# clock_led.net
KiCad netlist of a schematic drawn in Altium Designer
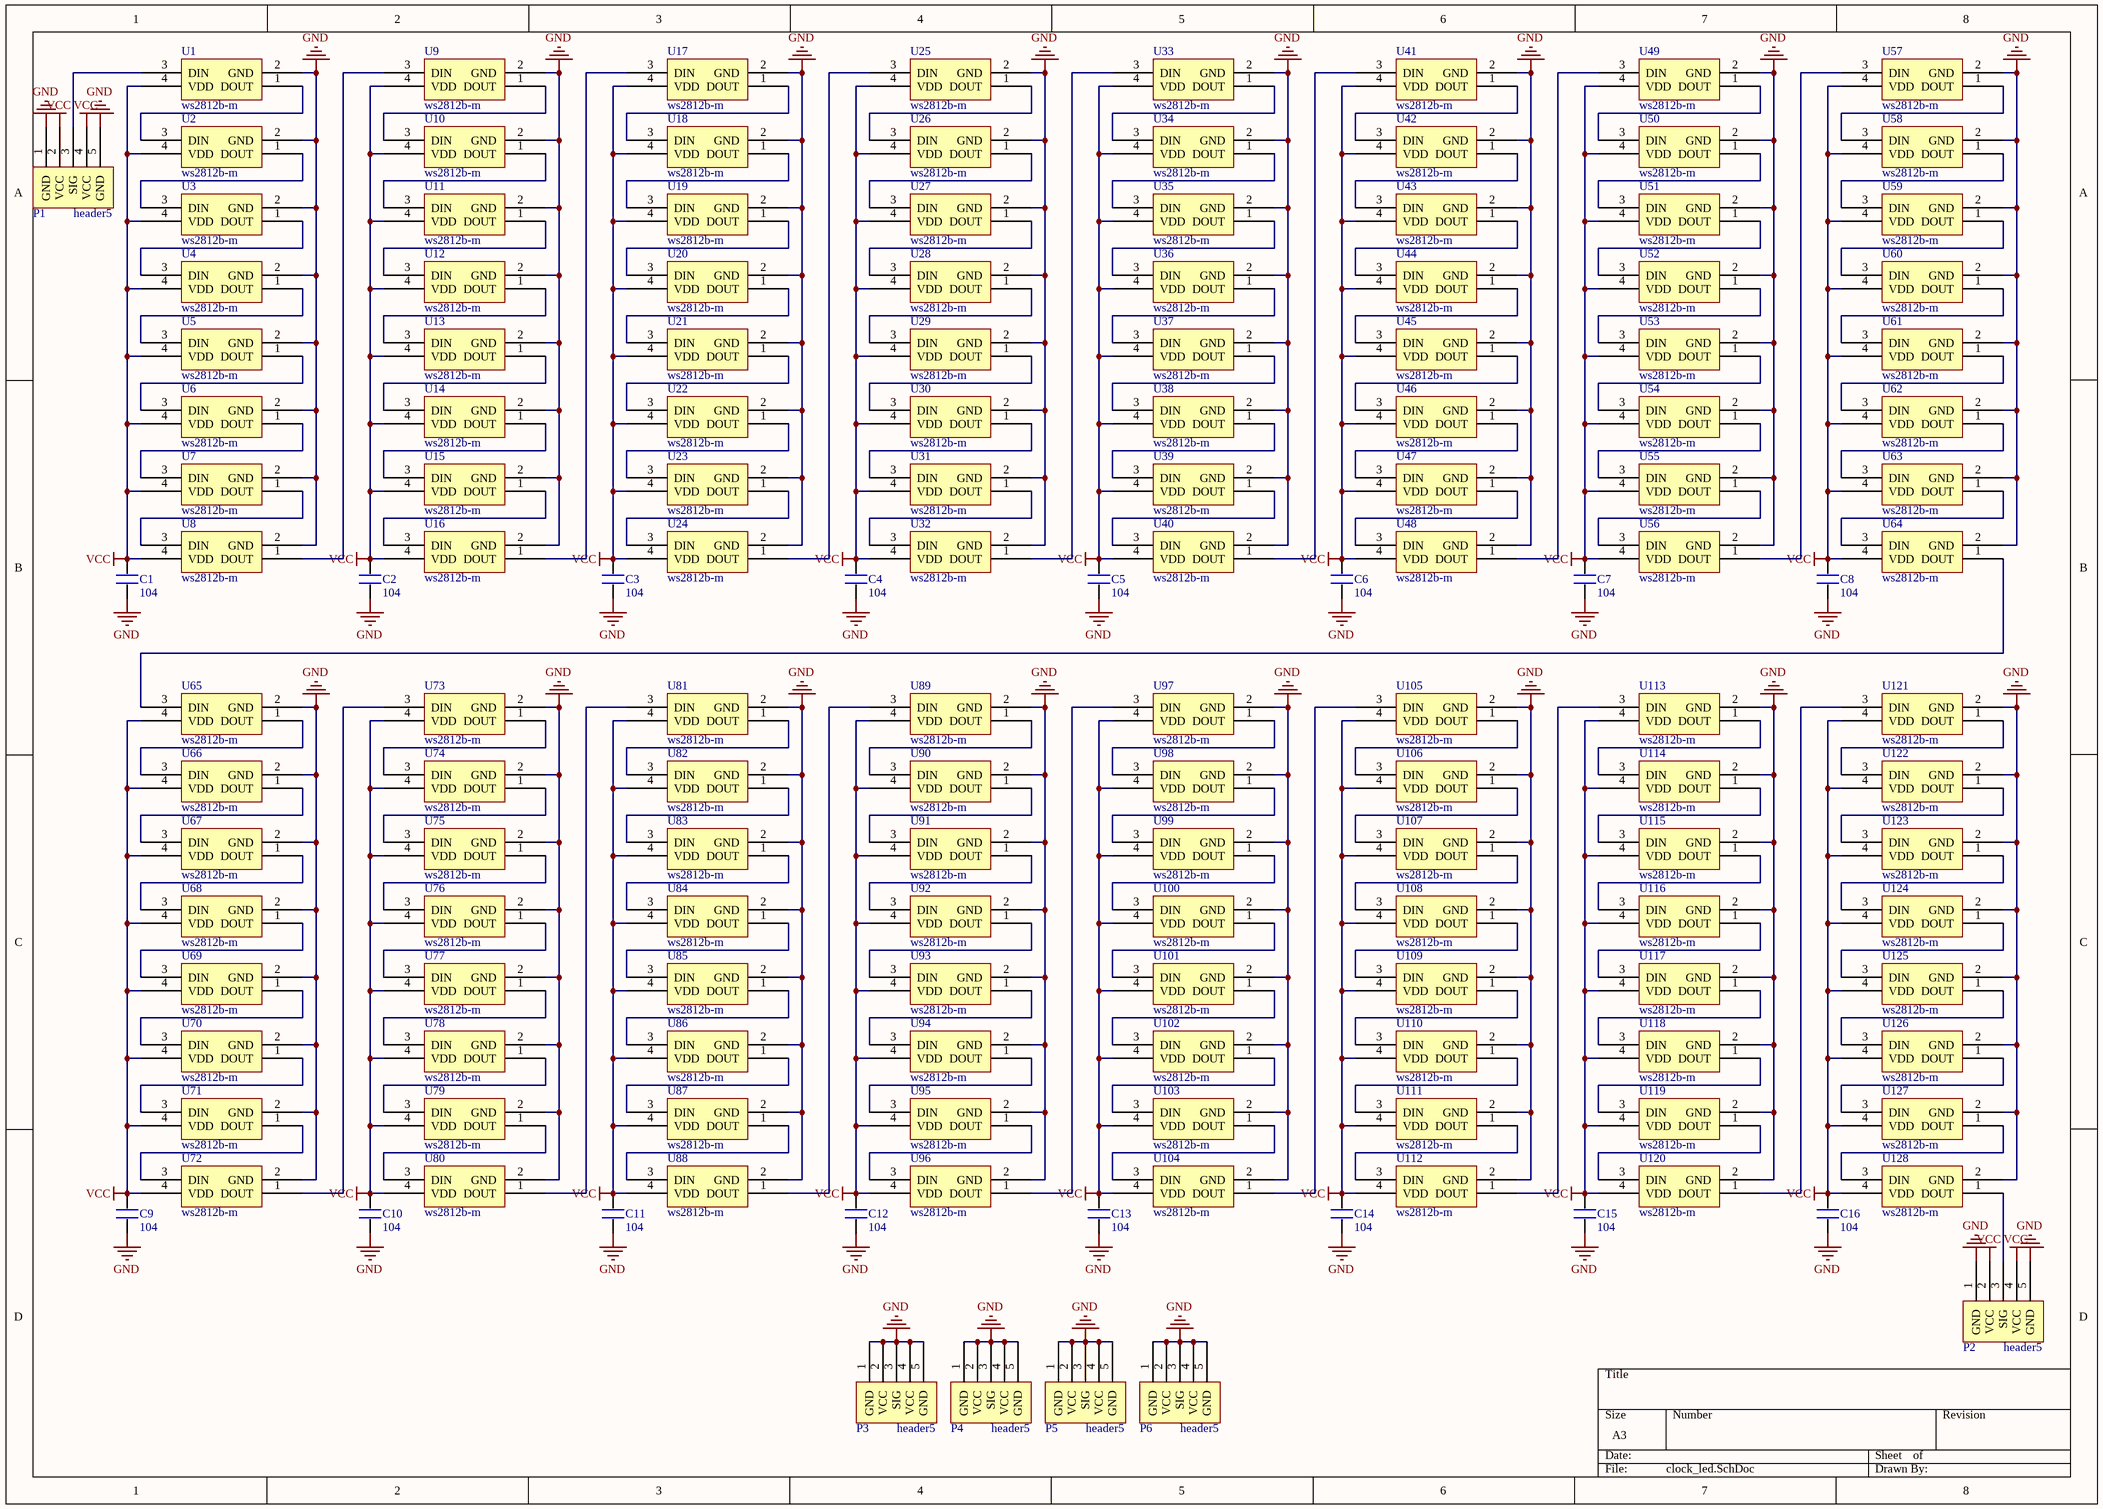
[diagram p0: clock_led.SchDoc]

(export (version "E")
  (design (tool "Eeschema 10.0.6"))
  (components
    (comp (ref "C1") (value "104") (footprint "0603P") (libsource (lib "WarShip V3 STM32103封装库") (part "C")))
    (comp (ref "C2") (value "104") (footprint "0603P") (libsource (lib "WarShip V3 STM32103封装库") (part "C")))
    (comp (ref "C3") (value "104") (footprint "0603P") (libsource (lib "WarShip V3 STM32103封装库") (part "C")))
    (comp (ref "C4") (value "104") (footprint "0603P") (libsource (lib "WarShip V3 STM32103封装库") (part "C")))
    (comp (ref "C5") (value "104") (footprint "0603P") (libsource (lib "WarShip V3 STM32103封装库") (part "C")))
    (comp (ref "C6") (value "104") (footprint "0603P") (libsource (lib "WarShip V3 STM32103封装库") (part "C")))
    (comp (ref "C7") (value "104") (footprint "0603P") (libsource (lib "WarShip V3 STM32103封装库") (part "C")))
    (comp (ref "C8") (value "104") (footprint "0603P") (libsource (lib "WarShip V3 STM32103封装库") (part "C")))
    (comp (ref "C9") (value "104") (footprint "0603P") (libsource (lib "WarShip V3 STM32103封装库") (part "C")))
    (comp (ref "C10") (value "104") (footprint "0603P") (libsource (lib "WarShip V3 STM32103封装库") (part "C")))
    (comp (ref "C11") (value "104") (footprint "0603P") (libsource (lib "WarShip V3 STM32103封装库") (part "C")))
    (comp (ref "C12") (value "104") (footprint "0603P") (libsource (lib "WarShip V3 STM32103封装库") (part "C")))
    (comp (ref "C13") (value "104") (footprint "0603P") (libsource (lib "WarShip V3 STM32103封装库") (part "C")))
    (comp (ref "C14") (value "104") (footprint "0603P") (libsource (lib "WarShip V3 STM32103封装库") (part "C")))
    (comp (ref "C15") (value "104") (footprint "0603P") (libsource (lib "WarShip V3 STM32103封装库") (part "C")))
    (comp (ref "C16") (value "104") (footprint "0603P") (libsource (lib "WarShip V3 STM32103封装库") (part "C")))
    (comp (ref "P1") (value "header5") (footprint "header5") (libsource (lib "clock") (part "header5")))
    (comp (ref "P2") (value "header5") (footprint "header5") (libsource (lib "clock") (part "header5")))
    (comp (ref "P3") (value "header5") (footprint "header5") (libsource (lib "clock") (part "header5")))
    (comp (ref "P4") (value "header5") (footprint "header5") (libsource (lib "clock") (part "header5")))
    (comp (ref "P5") (value "header5") (footprint "header5") (libsource (lib "clock") (part "header5")))
    (comp (ref "P6") (value "header5") (footprint "header5") (libsource (lib "clock") (part "header5")))
    (comp (ref "U1")
      (value "ws2812b-m")
      (footprint "WS2812B-MINI")
      (libsource (lib "clock") (part "WS2812B-MINI"))
    )
    (comp (ref "U2")
      (value "ws2812b-m")
      (footprint "WS2812B-MINI")
      (libsource (lib "clock") (part "WS2812B-MINI"))
    )
    (comp (ref "U3")
      (value "ws2812b-m")
      (footprint "WS2812B-MINI")
      (libsource (lib "clock") (part "WS2812B-MINI"))
    )
    (comp (ref "U4")
      (value "ws2812b-m")
      (footprint "WS2812B-MINI")
      (libsource (lib "clock") (part "WS2812B-MINI"))
    )
    (comp (ref "U5")
      (value "ws2812b-m")
      (footprint "WS2812B-MINI")
      (libsource (lib "clock") (part "WS2812B-MINI"))
    )
    (comp (ref "U6")
      (value "ws2812b-m")
      (footprint "WS2812B-MINI")
      (libsource (lib "clock") (part "WS2812B-MINI"))
    )
    (comp (ref "U7")
      (value "ws2812b-m")
      (footprint "WS2812B-MINI")
      (libsource (lib "clock") (part "WS2812B-MINI"))
    )
    (comp (ref "U8")
      (value "ws2812b-m")
      (footprint "WS2812B-MINI")
      (libsource (lib "clock") (part "WS2812B-MINI"))
    )
    (comp (ref "U9")
      (value "ws2812b-m")
      (footprint "WS2812B-MINI")
      (libsource (lib "clock") (part "WS2812B-MINI"))
    )
    (comp (ref "U10")
      (value "ws2812b-m")
      (footprint "WS2812B-MINI")
      (libsource (lib "clock") (part "WS2812B-MINI"))
    )
    (comp (ref "U11")
      (value "ws2812b-m")
      (footprint "WS2812B-MINI")
      (libsource (lib "clock") (part "WS2812B-MINI"))
    )
    (comp (ref "U12")
      (value "ws2812b-m")
      (footprint "WS2812B-MINI")
      (libsource (lib "clock") (part "WS2812B-MINI"))
    )
    (comp (ref "U13")
      (value "ws2812b-m")
      (footprint "WS2812B-MINI")
      (libsource (lib "clock") (part "WS2812B-MINI"))
    )
    (comp (ref "U14")
      (value "ws2812b-m")
      (footprint "WS2812B-MINI")
      (libsource (lib "clock") (part "WS2812B-MINI"))
    )
    (comp (ref "U15")
      (value "ws2812b-m")
      (footprint "WS2812B-MINI")
      (libsource (lib "clock") (part "WS2812B-MINI"))
    )
    (comp (ref "U16")
      (value "ws2812b-m")
      (footprint "WS2812B-MINI")
      (libsource (lib "clock") (part "WS2812B-MINI"))
    )
    (comp (ref "U17")
      (value "ws2812b-m")
      (footprint "WS2812B-MINI")
      (libsource (lib "clock") (part "WS2812B-MINI"))
    )
    (comp (ref "U18")
      (value "ws2812b-m")
      (footprint "WS2812B-MINI")
      (libsource (lib "clock") (part "WS2812B-MINI"))
    )
    (comp (ref "U19")
      (value "ws2812b-m")
      (footprint "WS2812B-MINI")
      (libsource (lib "clock") (part "WS2812B-MINI"))
    )
    (comp (ref "U20")
      (value "ws2812b-m")
      (footprint "WS2812B-MINI")
      (libsource (lib "clock") (part "WS2812B-MINI"))
    )
    (comp (ref "U21")
      (value "ws2812b-m")
      (footprint "WS2812B-MINI")
      (libsource (lib "clock") (part "WS2812B-MINI"))
    )
    (comp (ref "U22")
      (value "ws2812b-m")
      (footprint "WS2812B-MINI")
      (libsource (lib "clock") (part "WS2812B-MINI"))
    )
    (comp (ref "U23")
      (value "ws2812b-m")
      (footprint "WS2812B-MINI")
      (libsource (lib "clock") (part "WS2812B-MINI"))
    )
    (comp (ref "U24")
      (value "ws2812b-m")
      (footprint "WS2812B-MINI")
      (libsource (lib "clock") (part "WS2812B-MINI"))
    )
    (comp (ref "U25")
      (value "ws2812b-m")
      (footprint "WS2812B-MINI")
      (libsource (lib "clock") (part "WS2812B-MINI"))
    )
    (comp (ref "U26")
      (value "ws2812b-m")
      (footprint "WS2812B-MINI")
      (libsource (lib "clock") (part "WS2812B-MINI"))
    )
    (comp (ref "U27")
      (value "ws2812b-m")
      (footprint "WS2812B-MINI")
      (libsource (lib "clock") (part "WS2812B-MINI"))
    )
    (comp (ref "U28")
      (value "ws2812b-m")
      (footprint "WS2812B-MINI")
      (libsource (lib "clock") (part "WS2812B-MINI"))
    )
    (comp (ref "U29")
      (value "ws2812b-m")
      (footprint "WS2812B-MINI")
      (libsource (lib "clock") (part "WS2812B-MINI"))
    )
    (comp (ref "U30")
      (value "ws2812b-m")
      (footprint "WS2812B-MINI")
      (libsource (lib "clock") (part "WS2812B-MINI"))
    )
    (comp (ref "U31")
      (value "ws2812b-m")
      (footprint "WS2812B-MINI")
      (libsource (lib "clock") (part "WS2812B-MINI"))
    )
    (comp (ref "U32")
      (value "ws2812b-m")
      (footprint "WS2812B-MINI")
      (libsource (lib "clock") (part "WS2812B-MINI"))
    )
    (comp (ref "U33")
      (value "ws2812b-m")
      (footprint "WS2812B-MINI")
      (libsource (lib "clock") (part "WS2812B-MINI"))
    )
    (comp (ref "U34")
      (value "ws2812b-m")
      (footprint "WS2812B-MINI")
      (libsource (lib "clock") (part "WS2812B-MINI"))
    )
    (comp (ref "U35")
      (value "ws2812b-m")
      (footprint "WS2812B-MINI")
      (libsource (lib "clock") (part "WS2812B-MINI"))
    )
    (comp (ref "U36")
      (value "ws2812b-m")
      (footprint "WS2812B-MINI")
      (libsource (lib "clock") (part "WS2812B-MINI"))
    )
    (comp (ref "U37")
      (value "ws2812b-m")
      (footprint "WS2812B-MINI")
      (libsource (lib "clock") (part "WS2812B-MINI"))
    )
    (comp (ref "U38")
      (value "ws2812b-m")
      (footprint "WS2812B-MINI")
      (libsource (lib "clock") (part "WS2812B-MINI"))
    )
    (comp (ref "U39")
      (value "ws2812b-m")
      (footprint "WS2812B-MINI")
      (libsource (lib "clock") (part "WS2812B-MINI"))
    )
    (comp (ref "U40")
      (value "ws2812b-m")
      (footprint "WS2812B-MINI")
      (libsource (lib "clock") (part "WS2812B-MINI"))
    )
    (comp (ref "U41")
      (value "ws2812b-m")
      (footprint "WS2812B-MINI")
      (libsource (lib "clock") (part "WS2812B-MINI"))
    )
    (comp (ref "U42")
      (value "ws2812b-m")
      (footprint "WS2812B-MINI")
      (libsource (lib "clock") (part "WS2812B-MINI"))
    )
    (comp (ref "U43")
      (value "ws2812b-m")
      (footprint "WS2812B-MINI")
      (libsource (lib "clock") (part "WS2812B-MINI"))
    )
    (comp (ref "U44")
      (value "ws2812b-m")
      (footprint "WS2812B-MINI")
      (libsource (lib "clock") (part "WS2812B-MINI"))
    )
    (comp (ref "U45")
      (value "ws2812b-m")
      (footprint "WS2812B-MINI")
      (libsource (lib "clock") (part "WS2812B-MINI"))
    )
    (comp (ref "U46")
      (value "ws2812b-m")
      (footprint "WS2812B-MINI")
      (libsource (lib "clock") (part "WS2812B-MINI"))
    )
    (comp (ref "U47")
      (value "ws2812b-m")
      (footprint "WS2812B-MINI")
      (libsource (lib "clock") (part "WS2812B-MINI"))
    )
    (comp (ref "U48")
      (value "ws2812b-m")
      (footprint "WS2812B-MINI")
      (libsource (lib "clock") (part "WS2812B-MINI"))
    )
    (comp (ref "U49")
      (value "ws2812b-m")
      (footprint "WS2812B-MINI")
      (libsource (lib "clock") (part "WS2812B-MINI"))
    )
    (comp (ref "U50")
      (value "ws2812b-m")
      (footprint "WS2812B-MINI")
      (libsource (lib "clock") (part "WS2812B-MINI"))
    )
    (comp (ref "U51")
      (value "ws2812b-m")
      (footprint "WS2812B-MINI")
      (libsource (lib "clock") (part "WS2812B-MINI"))
    )
    (comp (ref "U52")
      (value "ws2812b-m")
      (footprint "WS2812B-MINI")
      (libsource (lib "clock") (part "WS2812B-MINI"))
    )
    (comp (ref "U53")
      (value "ws2812b-m")
      (footprint "WS2812B-MINI")
      (libsource (lib "clock") (part "WS2812B-MINI"))
    )
    (comp (ref "U54")
      (value "ws2812b-m")
      (footprint "WS2812B-MINI")
      (libsource (lib "clock") (part "WS2812B-MINI"))
    )
    (comp (ref "U55")
      (value "ws2812b-m")
      (footprint "WS2812B-MINI")
      (libsource (lib "clock") (part "WS2812B-MINI"))
    )
    (comp (ref "U56")
      (value "ws2812b-m")
      (footprint "WS2812B-MINI")
      (libsource (lib "clock") (part "WS2812B-MINI"))
    )
    (comp (ref "U57")
      (value "ws2812b-m")
      (footprint "WS2812B-MINI")
      (libsource (lib "clock") (part "WS2812B-MINI"))
    )
    (comp (ref "U58")
      (value "ws2812b-m")
      (footprint "WS2812B-MINI")
      (libsource (lib "clock") (part "WS2812B-MINI"))
    )
    (comp (ref "U59")
      (value "ws2812b-m")
      (footprint "WS2812B-MINI")
      (libsource (lib "clock") (part "WS2812B-MINI"))
    )
    (comp (ref "U60")
      (value "ws2812b-m")
      (footprint "WS2812B-MINI")
      (libsource (lib "clock") (part "WS2812B-MINI"))
    )
    (comp (ref "U61")
      (value "ws2812b-m")
      (footprint "WS2812B-MINI")
      (libsource (lib "clock") (part "WS2812B-MINI"))
    )
    (comp (ref "U62")
      (value "ws2812b-m")
      (footprint "WS2812B-MINI")
      (libsource (lib "clock") (part "WS2812B-MINI"))
    )
    (comp (ref "U63")
      (value "ws2812b-m")
      (footprint "WS2812B-MINI")
      (libsource (lib "clock") (part "WS2812B-MINI"))
    )
    (comp (ref "U64")
      (value "ws2812b-m")
      (footprint "WS2812B-MINI")
      (libsource (lib "clock") (part "WS2812B-MINI"))
    )
    (comp (ref "U65")
      (value "ws2812b-m")
      (footprint "WS2812B-MINI")
      (libsource (lib "clock") (part "WS2812B-MINI"))
    )
    (comp (ref "U66")
      (value "ws2812b-m")
      (footprint "WS2812B-MINI")
      (libsource (lib "clock") (part "WS2812B-MINI"))
    )
    (comp (ref "U67")
      (value "ws2812b-m")
      (footprint "WS2812B-MINI")
      (libsource (lib "clock") (part "WS2812B-MINI"))
    )
    (comp (ref "U68")
      (value "ws2812b-m")
      (footprint "WS2812B-MINI")
      (libsource (lib "clock") (part "WS2812B-MINI"))
    )
    (comp (ref "U69")
      (value "ws2812b-m")
      (footprint "WS2812B-MINI")
      (libsource (lib "clock") (part "WS2812B-MINI"))
    )
    (comp (ref "U70")
      (value "ws2812b-m")
      (footprint "WS2812B-MINI")
      (libsource (lib "clock") (part "WS2812B-MINI"))
    )
    (comp (ref "U71")
      (value "ws2812b-m")
      (footprint "WS2812B-MINI")
      (libsource (lib "clock") (part "WS2812B-MINI"))
    )
    (comp (ref "U72")
      (value "ws2812b-m")
      (footprint "WS2812B-MINI")
      (libsource (lib "clock") (part "WS2812B-MINI"))
    )
    (comp (ref "U73")
      (value "ws2812b-m")
      (footprint "WS2812B-MINI")
      (libsource (lib "clock") (part "WS2812B-MINI"))
    )
    (comp (ref "U74")
      (value "ws2812b-m")
      (footprint "WS2812B-MINI")
      (libsource (lib "clock") (part "WS2812B-MINI"))
    )
    (comp (ref "U75")
      (value "ws2812b-m")
      (footprint "WS2812B-MINI")
      (libsource (lib "clock") (part "WS2812B-MINI"))
    )
    (comp (ref "U76")
      (value "ws2812b-m")
      (footprint "WS2812B-MINI")
      (libsource (lib "clock") (part "WS2812B-MINI"))
    )
    (comp (ref "U77")
      (value "ws2812b-m")
      (footprint "WS2812B-MINI")
      (libsource (lib "clock") (part "WS2812B-MINI"))
    )
    (comp (ref "U78")
      (value "ws2812b-m")
      (footprint "WS2812B-MINI")
      (libsource (lib "clock") (part "WS2812B-MINI"))
    )
    (comp (ref "U79")
      (value "ws2812b-m")
      (footprint "WS2812B-MINI")
      (libsource (lib "clock") (part "WS2812B-MINI"))
    )
    (comp (ref "U80")
      (value "ws2812b-m")
      (footprint "WS2812B-MINI")
      (libsource (lib "clock") (part "WS2812B-MINI"))
    )
    (comp (ref "U81")
      (value "ws2812b-m")
      (footprint "WS2812B-MINI")
      (libsource (lib "clock") (part "WS2812B-MINI"))
    )
    (comp (ref "U82")
      (value "ws2812b-m")
      (footprint "WS2812B-MINI")
      (libsource (lib "clock") (part "WS2812B-MINI"))
    )
    (comp (ref "U83")
      (value "ws2812b-m")
      (footprint "WS2812B-MINI")
      (libsource (lib "clock") (part "WS2812B-MINI"))
    )
    (comp (ref "U84")
      (value "ws2812b-m")
      (footprint "WS2812B-MINI")
      (libsource (lib "clock") (part "WS2812B-MINI"))
    )
    (comp (ref "U85")
      (value "ws2812b-m")
      (footprint "WS2812B-MINI")
      (libsource (lib "clock") (part "WS2812B-MINI"))
    )
    (comp (ref "U86")
      (value "ws2812b-m")
      (footprint "WS2812B-MINI")
      (libsource (lib "clock") (part "WS2812B-MINI"))
    )
    (comp (ref "U87")
      (value "ws2812b-m")
      (footprint "WS2812B-MINI")
      (libsource (lib "clock") (part "WS2812B-MINI"))
    )
    (comp (ref "U88")
      (value "ws2812b-m")
      (footprint "WS2812B-MINI")
      (libsource (lib "clock") (part "WS2812B-MINI"))
    )
    (comp (ref "U89")
      (value "ws2812b-m")
      (footprint "WS2812B-MINI")
      (libsource (lib "clock") (part "WS2812B-MINI"))
    )
    (comp (ref "U90")
      (value "ws2812b-m")
      (footprint "WS2812B-MINI")
      (libsource (lib "clock") (part "WS2812B-MINI"))
    )
    (comp (ref "U91")
      (value "ws2812b-m")
      (footprint "WS2812B-MINI")
      (libsource (lib "clock") (part "WS2812B-MINI"))
    )
    (comp (ref "U92")
      (value "ws2812b-m")
      (footprint "WS2812B-MINI")
      (libsource (lib "clock") (part "WS2812B-MINI"))
    )
    (comp (ref "U93")
      (value "ws2812b-m")
      (footprint "WS2812B-MINI")
      (libsource (lib "clock") (part "WS2812B-MINI"))
    )
    (comp (ref "U94")
      (value "ws2812b-m")
      (footprint "WS2812B-MINI")
      (libsource (lib "clock") (part "WS2812B-MINI"))
    )
    (comp (ref "U95")
      (value "ws2812b-m")
      (footprint "WS2812B-MINI")
      (libsource (lib "clock") (part "WS2812B-MINI"))
    )
    (comp (ref "U96")
      (value "ws2812b-m")
      (footprint "WS2812B-MINI")
      (libsource (lib "clock") (part "WS2812B-MINI"))
    )
    (comp (ref "U97")
      (value "ws2812b-m")
      (footprint "WS2812B-MINI")
      (libsource (lib "clock") (part "WS2812B-MINI"))
    )
    (comp (ref "U98")
      (value "ws2812b-m")
      (footprint "WS2812B-MINI")
      (libsource (lib "clock") (part "WS2812B-MINI"))
    )
    (comp (ref "U99")
      (value "ws2812b-m")
      (footprint "WS2812B-MINI")
      (libsource (lib "clock") (part "WS2812B-MINI"))
    )
    (comp (ref "U100")
      (value "ws2812b-m")
      (footprint "WS2812B-MINI")
      (libsource (lib "clock") (part "WS2812B-MINI"))
    )
    (comp (ref "U101")
      (value "ws2812b-m")
      (footprint "WS2812B-MINI")
      (libsource (lib "clock") (part "WS2812B-MINI"))
    )
    (comp (ref "U102")
      (value "ws2812b-m")
      (footprint "WS2812B-MINI")
      (libsource (lib "clock") (part "WS2812B-MINI"))
    )
    (comp (ref "U103")
      (value "ws2812b-m")
      (footprint "WS2812B-MINI")
      (libsource (lib "clock") (part "WS2812B-MINI"))
    )
    (comp (ref "U104")
      (value "ws2812b-m")
      (footprint "WS2812B-MINI")
      (libsource (lib "clock") (part "WS2812B-MINI"))
    )
    (comp (ref "U105")
      (value "ws2812b-m")
      (footprint "WS2812B-MINI")
      (libsource (lib "clock") (part "WS2812B-MINI"))
    )
    (comp (ref "U106")
      (value "ws2812b-m")
      (footprint "WS2812B-MINI")
      (libsource (lib "clock") (part "WS2812B-MINI"))
    )
    (comp (ref "U107")
      (value "ws2812b-m")
      (footprint "WS2812B-MINI")
      (libsource (lib "clock") (part "WS2812B-MINI"))
    )
    (comp (ref "U108")
      (value "ws2812b-m")
      (footprint "WS2812B-MINI")
      (libsource (lib "clock") (part "WS2812B-MINI"))
    )
    (comp (ref "U109")
      (value "ws2812b-m")
      (footprint "WS2812B-MINI")
      (libsource (lib "clock") (part "WS2812B-MINI"))
    )
    (comp (ref "U110")
      (value "ws2812b-m")
      (footprint "WS2812B-MINI")
      (libsource (lib "clock") (part "WS2812B-MINI"))
    )
    (comp (ref "U111")
      (value "ws2812b-m")
      (footprint "WS2812B-MINI")
      (libsource (lib "clock") (part "WS2812B-MINI"))
    )
    (comp (ref "U112")
      (value "ws2812b-m")
      (footprint "WS2812B-MINI")
      (libsource (lib "clock") (part "WS2812B-MINI"))
    )
    (comp (ref "U113")
      (value "ws2812b-m")
      (footprint "WS2812B-MINI")
      (libsource (lib "clock") (part "WS2812B-MINI"))
    )
    (comp (ref "U114")
      (value "ws2812b-m")
      (footprint "WS2812B-MINI")
      (libsource (lib "clock") (part "WS2812B-MINI"))
    )
    (comp (ref "U115")
      (value "ws2812b-m")
      (footprint "WS2812B-MINI")
      (libsource (lib "clock") (part "WS2812B-MINI"))
    )
    (comp (ref "U116")
      (value "ws2812b-m")
      (footprint "WS2812B-MINI")
      (libsource (lib "clock") (part "WS2812B-MINI"))
    )
    (comp (ref "U117")
      (value "ws2812b-m")
      (footprint "WS2812B-MINI")
      (libsource (lib "clock") (part "WS2812B-MINI"))
    )
    (comp (ref "U118")
      (value "ws2812b-m")
      (footprint "WS2812B-MINI")
      (libsource (lib "clock") (part "WS2812B-MINI"))
    )
    (comp (ref "U119")
      (value "ws2812b-m")
      (footprint "WS2812B-MINI")
      (libsource (lib "clock") (part "WS2812B-MINI"))
    )
    (comp (ref "U120")
      (value "ws2812b-m")
      (footprint "WS2812B-MINI")
      (libsource (lib "clock") (part "WS2812B-MINI"))
    )
    (comp (ref "U121")
      (value "ws2812b-m")
      (footprint "WS2812B-MINI")
      (libsource (lib "clock") (part "WS2812B-MINI"))
    )
    (comp (ref "U122")
      (value "ws2812b-m")
      (footprint "WS2812B-MINI")
      (libsource (lib "clock") (part "WS2812B-MINI"))
    )
    (comp (ref "U123")
      (value "ws2812b-m")
      (footprint "WS2812B-MINI")
      (libsource (lib "clock") (part "WS2812B-MINI"))
    )
    (comp (ref "U124")
      (value "ws2812b-m")
      (footprint "WS2812B-MINI")
      (libsource (lib "clock") (part "WS2812B-MINI"))
    )
    (comp (ref "U125")
      (value "ws2812b-m")
      (footprint "WS2812B-MINI")
      (libsource (lib "clock") (part "WS2812B-MINI"))
    )
    (comp (ref "U126")
      (value "ws2812b-m")
      (footprint "WS2812B-MINI")
      (libsource (lib "clock") (part "WS2812B-MINI"))
    )
    (comp (ref "U127")
      (value "ws2812b-m")
      (footprint "WS2812B-MINI")
      (libsource (lib "clock") (part "WS2812B-MINI"))
    )
    (comp (ref "U128")
      (value "ws2812b-m")
      (footprint "WS2812B-MINI")
      (libsource (lib "clock") (part "WS2812B-MINI"))
    )
  )
  (nets
    (net (code "1") (name "GND") (class "Default")
      (node (ref "C1") (pin "1") (pintype "passive"))
      (node (ref "C10") (pin "1") (pintype "passive"))
      (node (ref "C11") (pin "1") (pintype "passive"))
      (node (ref "C12") (pin "1") (pintype "passive"))
      (node (ref "C13") (pin "1") (pintype "passive"))
      (node (ref "C14") (pin "1") (pintype "passive"))
      (node (ref "C15") (pin "1") (pintype "passive"))
      (node (ref "C16") (pin "1") (pintype "passive"))
      (node (ref "C2") (pin "1") (pintype "passive"))
      (node (ref "C3") (pin "1") (pintype "passive"))
      (node (ref "C4") (pin "1") (pintype "passive"))
      (node (ref "C5") (pin "1") (pintype "passive"))
      (node (ref "C6") (pin "1") (pintype "passive"))
      (node (ref "C7") (pin "1") (pintype "passive"))
      (node (ref "C8") (pin "1") (pintype "passive"))
      (node (ref "C9") (pin "1") (pintype "passive"))
      (node (ref "P1") (pin "1") (pinfunction "GND_1") (pintype "passive"))
      (node (ref "P1") (pin "5") (pinfunction "GND_5") (pintype "passive"))
      (node (ref "P2") (pin "1") (pinfunction "GND_1") (pintype "passive"))
      (node (ref "P2") (pin "5") (pinfunction "GND_5") (pintype "passive"))
      (node (ref "P3") (pin "1") (pinfunction "GND_1") (pintype "passive"))
      (node (ref "P3") (pin "2") (pinfunction "VCC_2") (pintype "passive"))
      (node (ref "P3") (pin "3") (pinfunction "SIG_3") (pintype "passive"))
      (node (ref "P3") (pin "4") (pinfunction "VCC_4") (pintype "passive"))
      (node (ref "P3") (pin "5") (pinfunction "GND_5") (pintype "passive"))
      (node (ref "P4") (pin "1") (pinfunction "GND_1") (pintype "passive"))
      (node (ref "P4") (pin "2") (pinfunction "VCC_2") (pintype "passive"))
      (node (ref "P4") (pin "3") (pinfunction "SIG_3") (pintype "passive"))
      (node (ref "P4") (pin "4") (pinfunction "VCC_4") (pintype "passive"))
      (node (ref "P4") (pin "5") (pinfunction "GND_5") (pintype "passive"))
      (node (ref "P5") (pin "1") (pinfunction "GND_1") (pintype "passive"))
      (node (ref "P5") (pin "2") (pinfunction "VCC_2") (pintype "passive"))
      (node (ref "P5") (pin "3") (pinfunction "SIG_3") (pintype "passive"))
      (node (ref "P5") (pin "4") (pinfunction "VCC_4") (pintype "passive"))
      (node (ref "P5") (pin "5") (pinfunction "GND_5") (pintype "passive"))
      (node (ref "P6") (pin "1") (pinfunction "GND_1") (pintype "passive"))
      (node (ref "P6") (pin "2") (pinfunction "VCC_2") (pintype "passive"))
      (node (ref "P6") (pin "3") (pinfunction "SIG_3") (pintype "passive"))
      (node (ref "P6") (pin "4") (pinfunction "VCC_4") (pintype "passive"))
      (node (ref "P6") (pin "5") (pinfunction "GND_5") (pintype "passive"))
      (node (ref "U1") (pin "2") (pinfunction "GND_2") (pintype "passive"))
      (node (ref "U10") (pin "2") (pinfunction "GND_2") (pintype "passive"))
      (node (ref "U100") (pin "2") (pinfunction "GND_2") (pintype "passive"))
      (node (ref "U101") (pin "2") (pinfunction "GND_2") (pintype "passive"))
      (node (ref "U102") (pin "2") (pinfunction "GND_2") (pintype "passive"))
      (node (ref "U103") (pin "2") (pinfunction "GND_2") (pintype "passive"))
      (node (ref "U104") (pin "2") (pinfunction "GND_2") (pintype "passive"))
      (node (ref "U105") (pin "2") (pinfunction "GND_2") (pintype "passive"))
      (node (ref "U106") (pin "2") (pinfunction "GND_2") (pintype "passive"))
      (node (ref "U107") (pin "2") (pinfunction "GND_2") (pintype "passive"))
      (node (ref "U108") (pin "2") (pinfunction "GND_2") (pintype "passive"))
      (node (ref "U109") (pin "2") (pinfunction "GND_2") (pintype "passive"))
      (node (ref "U11") (pin "2") (pinfunction "GND_2") (pintype "passive"))
      (node (ref "U110") (pin "2") (pinfunction "GND_2") (pintype "passive"))
      (node (ref "U111") (pin "2") (pinfunction "GND_2") (pintype "passive"))
      (node (ref "U112") (pin "2") (pinfunction "GND_2") (pintype "passive"))
      (node (ref "U113") (pin "2") (pinfunction "GND_2") (pintype "passive"))
      (node (ref "U114") (pin "2") (pinfunction "GND_2") (pintype "passive"))
      (node (ref "U115") (pin "2") (pinfunction "GND_2") (pintype "passive"))
      (node (ref "U116") (pin "2") (pinfunction "GND_2") (pintype "passive"))
      (node (ref "U117") (pin "2") (pinfunction "GND_2") (pintype "passive"))
      (node (ref "U118") (pin "2") (pinfunction "GND_2") (pintype "passive"))
      (node (ref "U119") (pin "2") (pinfunction "GND_2") (pintype "passive"))
      (node (ref "U12") (pin "2") (pinfunction "GND_2") (pintype "passive"))
      (node (ref "U120") (pin "2") (pinfunction "GND_2") (pintype "passive"))
      (node (ref "U121") (pin "2") (pinfunction "GND_2") (pintype "passive"))
      (node (ref "U122") (pin "2") (pinfunction "GND_2") (pintype "passive"))
      (node (ref "U123") (pin "2") (pinfunction "GND_2") (pintype "passive"))
      (node (ref "U124") (pin "2") (pinfunction "GND_2") (pintype "passive"))
      (node (ref "U125") (pin "2") (pinfunction "GND_2") (pintype "passive"))
      (node (ref "U126") (pin "2") (pinfunction "GND_2") (pintype "passive"))
      (node (ref "U127") (pin "2") (pinfunction "GND_2") (pintype "passive"))
      (node (ref "U128") (pin "2") (pinfunction "GND_2") (pintype "passive"))
      (node (ref "U13") (pin "2") (pinfunction "GND_2") (pintype "passive"))
      (node (ref "U14") (pin "2") (pinfunction "GND_2") (pintype "passive"))
      (node (ref "U15") (pin "2") (pinfunction "GND_2") (pintype "passive"))
      (node (ref "U16") (pin "2") (pinfunction "GND_2") (pintype "passive"))
      (node (ref "U17") (pin "2") (pinfunction "GND_2") (pintype "passive"))
      (node (ref "U18") (pin "2") (pinfunction "GND_2") (pintype "passive"))
      (node (ref "U19") (pin "2") (pinfunction "GND_2") (pintype "passive"))
      (node (ref "U2") (pin "2") (pinfunction "GND_2") (pintype "passive"))
      (node (ref "U20") (pin "2") (pinfunction "GND_2") (pintype "passive"))
      (node (ref "U21") (pin "2") (pinfunction "GND_2") (pintype "passive"))
      (node (ref "U22") (pin "2") (pinfunction "GND_2") (pintype "passive"))
      (node (ref "U23") (pin "2") (pinfunction "GND_2") (pintype "passive"))
      (node (ref "U24") (pin "2") (pinfunction "GND_2") (pintype "passive"))
      (node (ref "U25") (pin "2") (pinfunction "GND_2") (pintype "passive"))
      (node (ref "U26") (pin "2") (pinfunction "GND_2") (pintype "passive"))
      (node (ref "U27") (pin "2") (pinfunction "GND_2") (pintype "passive"))
      (node (ref "U28") (pin "2") (pinfunction "GND_2") (pintype "passive"))
      (node (ref "U29") (pin "2") (pinfunction "GND_2") (pintype "passive"))
      (node (ref "U3") (pin "2") (pinfunction "GND_2") (pintype "passive"))
      (node (ref "U30") (pin "2") (pinfunction "GND_2") (pintype "passive"))
      (node (ref "U31") (pin "2") (pinfunction "GND_2") (pintype "passive"))
      (node (ref "U32") (pin "2") (pinfunction "GND_2") (pintype "passive"))
      (node (ref "U33") (pin "2") (pinfunction "GND_2") (pintype "passive"))
      (node (ref "U34") (pin "2") (pinfunction "GND_2") (pintype "passive"))
      (node (ref "U35") (pin "2") (pinfunction "GND_2") (pintype "passive"))
      (node (ref "U36") (pin "2") (pinfunction "GND_2") (pintype "passive"))
      (node (ref "U37") (pin "2") (pinfunction "GND_2") (pintype "passive"))
      (node (ref "U38") (pin "2") (pinfunction "GND_2") (pintype "passive"))
      (node (ref "U39") (pin "2") (pinfunction "GND_2") (pintype "passive"))
      (node (ref "U4") (pin "2") (pinfunction "GND_2") (pintype "passive"))
      (node (ref "U40") (pin "2") (pinfunction "GND_2") (pintype "passive"))
      (node (ref "U41") (pin "2") (pinfunction "GND_2") (pintype "passive"))
      (node (ref "U42") (pin "2") (pinfunction "GND_2") (pintype "passive"))
      (node (ref "U43") (pin "2") (pinfunction "GND_2") (pintype "passive"))
      (node (ref "U44") (pin "2") (pinfunction "GND_2") (pintype "passive"))
      (node (ref "U45") (pin "2") (pinfunction "GND_2") (pintype "passive"))
      (node (ref "U46") (pin "2") (pinfunction "GND_2") (pintype "passive"))
      (node (ref "U47") (pin "2") (pinfunction "GND_2") (pintype "passive"))
      (node (ref "U48") (pin "2") (pinfunction "GND_2") (pintype "passive"))
      (node (ref "U49") (pin "2") (pinfunction "GND_2") (pintype "passive"))
      (node (ref "U5") (pin "2") (pinfunction "GND_2") (pintype "passive"))
      (node (ref "U50") (pin "2") (pinfunction "GND_2") (pintype "passive"))
      (node (ref "U51") (pin "2") (pinfunction "GND_2") (pintype "passive"))
      (node (ref "U52") (pin "2") (pinfunction "GND_2") (pintype "passive"))
      (node (ref "U53") (pin "2") (pinfunction "GND_2") (pintype "passive"))
      (node (ref "U54") (pin "2") (pinfunction "GND_2") (pintype "passive"))
      (node (ref "U55") (pin "2") (pinfunction "GND_2") (pintype "passive"))
      (node (ref "U56") (pin "2") (pinfunction "GND_2") (pintype "passive"))
      (node (ref "U57") (pin "2") (pinfunction "GND_2") (pintype "passive"))
      (node (ref "U58") (pin "2") (pinfunction "GND_2") (pintype "passive"))
      (node (ref "U59") (pin "2") (pinfunction "GND_2") (pintype "passive"))
      (node (ref "U6") (pin "2") (pinfunction "GND_2") (pintype "passive"))
      (node (ref "U60") (pin "2") (pinfunction "GND_2") (pintype "passive"))
      (node (ref "U61") (pin "2") (pinfunction "GND_2") (pintype "passive"))
      (node (ref "U62") (pin "2") (pinfunction "GND_2") (pintype "passive"))
      (node (ref "U63") (pin "2") (pinfunction "GND_2") (pintype "passive"))
      (node (ref "U64") (pin "2") (pinfunction "GND_2") (pintype "passive"))
      (node (ref "U65") (pin "2") (pinfunction "GND_2") (pintype "passive"))
      (node (ref "U66") (pin "2") (pinfunction "GND_2") (pintype "passive"))
      (node (ref "U67") (pin "2") (pinfunction "GND_2") (pintype "passive"))
      (node (ref "U68") (pin "2") (pinfunction "GND_2") (pintype "passive"))
      (node (ref "U69") (pin "2") (pinfunction "GND_2") (pintype "passive"))
      (node (ref "U7") (pin "2") (pinfunction "GND_2") (pintype "passive"))
      (node (ref "U70") (pin "2") (pinfunction "GND_2") (pintype "passive"))
      (node (ref "U71") (pin "2") (pinfunction "GND_2") (pintype "passive"))
      (node (ref "U72") (pin "2") (pinfunction "GND_2") (pintype "passive"))
      (node (ref "U73") (pin "2") (pinfunction "GND_2") (pintype "passive"))
      (node (ref "U74") (pin "2") (pinfunction "GND_2") (pintype "passive"))
      (node (ref "U75") (pin "2") (pinfunction "GND_2") (pintype "passive"))
      (node (ref "U76") (pin "2") (pinfunction "GND_2") (pintype "passive"))
      (node (ref "U77") (pin "2") (pinfunction "GND_2") (pintype "passive"))
      (node (ref "U78") (pin "2") (pinfunction "GND_2") (pintype "passive"))
      (node (ref "U79") (pin "2") (pinfunction "GND_2") (pintype "passive"))
      (node (ref "U8") (pin "2") (pinfunction "GND_2") (pintype "passive"))
      (node (ref "U80") (pin "2") (pinfunction "GND_2") (pintype "passive"))
      (node (ref "U81") (pin "2") (pinfunction "GND_2") (pintype "passive"))
      (node (ref "U82") (pin "2") (pinfunction "GND_2") (pintype "passive"))
      (node (ref "U83") (pin "2") (pinfunction "GND_2") (pintype "passive"))
      (node (ref "U84") (pin "2") (pinfunction "GND_2") (pintype "passive"))
      (node (ref "U85") (pin "2") (pinfunction "GND_2") (pintype "passive"))
      (node (ref "U86") (pin "2") (pinfunction "GND_2") (pintype "passive"))
      (node (ref "U87") (pin "2") (pinfunction "GND_2") (pintype "passive"))
      (node (ref "U88") (pin "2") (pinfunction "GND_2") (pintype "passive"))
      (node (ref "U89") (pin "2") (pinfunction "GND_2") (pintype "passive"))
      (node (ref "U9") (pin "2") (pinfunction "GND_2") (pintype "passive"))
      (node (ref "U90") (pin "2") (pinfunction "GND_2") (pintype "passive"))
      (node (ref "U91") (pin "2") (pinfunction "GND_2") (pintype "passive"))
      (node (ref "U92") (pin "2") (pinfunction "GND_2") (pintype "passive"))
      (node (ref "U93") (pin "2") (pinfunction "GND_2") (pintype "passive"))
      (node (ref "U94") (pin "2") (pinfunction "GND_2") (pintype "passive"))
      (node (ref "U95") (pin "2") (pinfunction "GND_2") (pintype "passive"))
      (node (ref "U96") (pin "2") (pinfunction "GND_2") (pintype "passive"))
      (node (ref "U97") (pin "2") (pinfunction "GND_2") (pintype "passive"))
      (node (ref "U98") (pin "2") (pinfunction "GND_2") (pintype "passive"))
      (node (ref "U99") (pin "2") (pinfunction "GND_2") (pintype "passive"))
    )
    (net (code "2") (name "Net-(P1-SIG)") (class "Default")
      (node (ref "P1") (pin "3") (pinfunction "SIG_3") (pintype "passive"))
      (node (ref "U1") (pin "3") (pinfunction "DIN_3") (pintype "passive"))
    )
    (net (code "3") (name "Net-(P2-SIG)") (class "Default")
      (node (ref "P2") (pin "3") (pinfunction "SIG_3") (pintype "passive"))
      (node (ref "U128") (pin "1") (pinfunction "DOUT_1") (pintype "passive"))
    )
    (net (code "4") (name "Net-(U1-DOUT)") (class "Default")
      (node (ref "U1") (pin "1") (pinfunction "DOUT_1") (pintype "passive"))
      (node (ref "U2") (pin "3") (pinfunction "DIN_3") (pintype "passive"))
    )
    (net (code "5") (name "Net-(U2-DOUT)") (class "Default")
      (node (ref "U2") (pin "1") (pinfunction "DOUT_1") (pintype "passive"))
      (node (ref "U3") (pin "3") (pinfunction "DIN_3") (pintype "passive"))
    )
    (net (code "6") (name "Net-(U3-DOUT)") (class "Default")
      (node (ref "U3") (pin "1") (pinfunction "DOUT_1") (pintype "passive"))
      (node (ref "U4") (pin "3") (pinfunction "DIN_3") (pintype "passive"))
    )
    (net (code "7") (name "Net-(U4-DOUT)") (class "Default")
      (node (ref "U4") (pin "1") (pinfunction "DOUT_1") (pintype "passive"))
      (node (ref "U5") (pin "3") (pinfunction "DIN_3") (pintype "passive"))
    )
    (net (code "8") (name "Net-(U5-DOUT)") (class "Default")
      (node (ref "U5") (pin "1") (pinfunction "DOUT_1") (pintype "passive"))
      (node (ref "U6") (pin "3") (pinfunction "DIN_3") (pintype "passive"))
    )
    (net (code "9") (name "Net-(U6-DOUT)") (class "Default")
      (node (ref "U6") (pin "1") (pinfunction "DOUT_1") (pintype "passive"))
      (node (ref "U7") (pin "3") (pinfunction "DIN_3") (pintype "passive"))
    )
    (net (code "10") (name "Net-(U7-DOUT)") (class "Default")
      (node (ref "U7") (pin "1") (pinfunction "DOUT_1") (pintype "passive"))
      (node (ref "U8") (pin "3") (pinfunction "DIN_3") (pintype "passive"))
    )
    (net (code "11") (name "Net-(U8-DOUT)") (class "Default")
      (node (ref "U8") (pin "1") (pinfunction "DOUT_1") (pintype "passive"))
      (node (ref "U9") (pin "3") (pinfunction "DIN_3") (pintype "passive"))
    )
    (net (code "12") (name "Net-(U10-DIN)") (class "Default")
      (node (ref "U10") (pin "3") (pinfunction "DIN_3") (pintype "passive"))
      (node (ref "U9") (pin "1") (pinfunction "DOUT_1") (pintype "passive"))
    )
    (net (code "13") (name "Net-(U10-DOUT)") (class "Default")
      (node (ref "U10") (pin "1") (pinfunction "DOUT_1") (pintype "passive"))
      (node (ref "U11") (pin "3") (pinfunction "DIN_3") (pintype "passive"))
    )
    (net (code "14") (name "Net-(U11-DOUT)") (class "Default")
      (node (ref "U11") (pin "1") (pinfunction "DOUT_1") (pintype "passive"))
      (node (ref "U12") (pin "3") (pinfunction "DIN_3") (pintype "passive"))
    )
    (net (code "15") (name "Net-(U12-DOUT)") (class "Default")
      (node (ref "U12") (pin "1") (pinfunction "DOUT_1") (pintype "passive"))
      (node (ref "U13") (pin "3") (pinfunction "DIN_3") (pintype "passive"))
    )
    (net (code "16") (name "Net-(U13-DOUT)") (class "Default")
      (node (ref "U13") (pin "1") (pinfunction "DOUT_1") (pintype "passive"))
      (node (ref "U14") (pin "3") (pinfunction "DIN_3") (pintype "passive"))
    )
    (net (code "17") (name "Net-(U14-DOUT)") (class "Default")
      (node (ref "U14") (pin "1") (pinfunction "DOUT_1") (pintype "passive"))
      (node (ref "U15") (pin "3") (pinfunction "DIN_3") (pintype "passive"))
    )
    (net (code "18") (name "Net-(U15-DOUT)") (class "Default")
      (node (ref "U15") (pin "1") (pinfunction "DOUT_1") (pintype "passive"))
      (node (ref "U16") (pin "3") (pinfunction "DIN_3") (pintype "passive"))
    )
    (net (code "19") (name "Net-(U16-DOUT)") (class "Default")
      (node (ref "U16") (pin "1") (pinfunction "DOUT_1") (pintype "passive"))
      (node (ref "U17") (pin "3") (pinfunction "DIN_3") (pintype "passive"))
    )
    (net (code "20") (name "Net-(U17-DOUT)") (class "Default")
      (node (ref "U17") (pin "1") (pinfunction "DOUT_1") (pintype "passive"))
      (node (ref "U18") (pin "3") (pinfunction "DIN_3") (pintype "passive"))
    )
    (net (code "21") (name "Net-(U18-DOUT)") (class "Default")
      (node (ref "U18") (pin "1") (pinfunction "DOUT_1") (pintype "passive"))
      (node (ref "U19") (pin "3") (pinfunction "DIN_3") (pintype "passive"))
    )
    (net (code "22") (name "Net-(U19-DOUT)") (class "Default")
      (node (ref "U19") (pin "1") (pinfunction "DOUT_1") (pintype "passive"))
      (node (ref "U20") (pin "3") (pinfunction "DIN_3") (pintype "passive"))
    )
    (net (code "23") (name "Net-(U20-DOUT)") (class "Default")
      (node (ref "U20") (pin "1") (pinfunction "DOUT_1") (pintype "passive"))
      (node (ref "U21") (pin "3") (pinfunction "DIN_3") (pintype "passive"))
    )
    (net (code "24") (name "Net-(U21-DOUT)") (class "Default")
      (node (ref "U21") (pin "1") (pinfunction "DOUT_1") (pintype "passive"))
      (node (ref "U22") (pin "3") (pinfunction "DIN_3") (pintype "passive"))
    )
    (net (code "25") (name "Net-(U22-DOUT)") (class "Default")
      (node (ref "U22") (pin "1") (pinfunction "DOUT_1") (pintype "passive"))
      (node (ref "U23") (pin "3") (pinfunction "DIN_3") (pintype "passive"))
    )
    (net (code "26") (name "Net-(U23-DOUT)") (class "Default")
      (node (ref "U23") (pin "1") (pinfunction "DOUT_1") (pintype "passive"))
      (node (ref "U24") (pin "3") (pinfunction "DIN_3") (pintype "passive"))
    )
    (net (code "27") (name "Net-(U24-DOUT)") (class "Default")
      (node (ref "U24") (pin "1") (pinfunction "DOUT_1") (pintype "passive"))
      (node (ref "U25") (pin "3") (pinfunction "DIN_3") (pintype "passive"))
    )
    (net (code "28") (name "Net-(U25-DOUT)") (class "Default")
      (node (ref "U25") (pin "1") (pinfunction "DOUT_1") (pintype "passive"))
      (node (ref "U26") (pin "3") (pinfunction "DIN_3") (pintype "passive"))
    )
    (net (code "29") (name "Net-(U26-DOUT)") (class "Default")
      (node (ref "U26") (pin "1") (pinfunction "DOUT_1") (pintype "passive"))
      (node (ref "U27") (pin "3") (pinfunction "DIN_3") (pintype "passive"))
    )
    (net (code "30") (name "Net-(U27-DOUT)") (class "Default")
      (node (ref "U27") (pin "1") (pinfunction "DOUT_1") (pintype "passive"))
      (node (ref "U28") (pin "3") (pinfunction "DIN_3") (pintype "passive"))
    )
    (net (code "31") (name "Net-(U28-DOUT)") (class "Default")
      (node (ref "U28") (pin "1") (pinfunction "DOUT_1") (pintype "passive"))
      (node (ref "U29") (pin "3") (pinfunction "DIN_3") (pintype "passive"))
    )
    (net (code "32") (name "Net-(U29-DOUT)") (class "Default")
      (node (ref "U29") (pin "1") (pinfunction "DOUT_1") (pintype "passive"))
      (node (ref "U30") (pin "3") (pinfunction "DIN_3") (pintype "passive"))
    )
    (net (code "33") (name "Net-(U30-DOUT)") (class "Default")
      (node (ref "U30") (pin "1") (pinfunction "DOUT_1") (pintype "passive"))
      (node (ref "U31") (pin "3") (pinfunction "DIN_3") (pintype "passive"))
    )
    (net (code "34") (name "Net-(U31-DOUT)") (class "Default")
      (node (ref "U31") (pin "1") (pinfunction "DOUT_1") (pintype "passive"))
      (node (ref "U32") (pin "3") (pinfunction "DIN_3") (pintype "passive"))
    )
    (net (code "35") (name "Net-(U32-DOUT)") (class "Default")
      (node (ref "U32") (pin "1") (pinfunction "DOUT_1") (pintype "passive"))
      (node (ref "U33") (pin "3") (pinfunction "DIN_3") (pintype "passive"))
    )
    (net (code "36") (name "Net-(U33-DOUT)") (class "Default")
      (node (ref "U33") (pin "1") (pinfunction "DOUT_1") (pintype "passive"))
      (node (ref "U34") (pin "3") (pinfunction "DIN_3") (pintype "passive"))
    )
    (net (code "37") (name "Net-(U34-DOUT)") (class "Default")
      (node (ref "U34") (pin "1") (pinfunction "DOUT_1") (pintype "passive"))
      (node (ref "U35") (pin "3") (pinfunction "DIN_3") (pintype "passive"))
    )
    (net (code "38") (name "Net-(U35-DOUT)") (class "Default")
      (node (ref "U35") (pin "1") (pinfunction "DOUT_1") (pintype "passive"))
      (node (ref "U36") (pin "3") (pinfunction "DIN_3") (pintype "passive"))
    )
    (net (code "39") (name "Net-(U36-DOUT)") (class "Default")
      (node (ref "U36") (pin "1") (pinfunction "DOUT_1") (pintype "passive"))
      (node (ref "U37") (pin "3") (pinfunction "DIN_3") (pintype "passive"))
    )
    (net (code "40") (name "Net-(U37-DOUT)") (class "Default")
      (node (ref "U37") (pin "1") (pinfunction "DOUT_1") (pintype "passive"))
      (node (ref "U38") (pin "3") (pinfunction "DIN_3") (pintype "passive"))
    )
    (net (code "41") (name "Net-(U38-DOUT)") (class "Default")
      (node (ref "U38") (pin "1") (pinfunction "DOUT_1") (pintype "passive"))
      (node (ref "U39") (pin "3") (pinfunction "DIN_3") (pintype "passive"))
    )
    (net (code "42") (name "Net-(U39-DOUT)") (class "Default")
      (node (ref "U39") (pin "1") (pinfunction "DOUT_1") (pintype "passive"))
      (node (ref "U40") (pin "3") (pinfunction "DIN_3") (pintype "passive"))
    )
    (net (code "43") (name "Net-(U40-DOUT)") (class "Default")
      (node (ref "U40") (pin "1") (pinfunction "DOUT_1") (pintype "passive"))
      (node (ref "U41") (pin "3") (pinfunction "DIN_3") (pintype "passive"))
    )
    (net (code "44") (name "Net-(U41-DOUT)") (class "Default")
      (node (ref "U41") (pin "1") (pinfunction "DOUT_1") (pintype "passive"))
      (node (ref "U42") (pin "3") (pinfunction "DIN_3") (pintype "passive"))
    )
    (net (code "45") (name "Net-(U42-DOUT)") (class "Default")
      (node (ref "U42") (pin "1") (pinfunction "DOUT_1") (pintype "passive"))
      (node (ref "U43") (pin "3") (pinfunction "DIN_3") (pintype "passive"))
    )
    (net (code "46") (name "Net-(U43-DOUT)") (class "Default")
      (node (ref "U43") (pin "1") (pinfunction "DOUT_1") (pintype "passive"))
      (node (ref "U44") (pin "3") (pinfunction "DIN_3") (pintype "passive"))
    )
    (net (code "47") (name "Net-(U44-DOUT)") (class "Default")
      (node (ref "U44") (pin "1") (pinfunction "DOUT_1") (pintype "passive"))
      (node (ref "U45") (pin "3") (pinfunction "DIN_3") (pintype "passive"))
    )
    (net (code "48") (name "Net-(U45-DOUT)") (class "Default")
      (node (ref "U45") (pin "1") (pinfunction "DOUT_1") (pintype "passive"))
      (node (ref "U46") (pin "3") (pinfunction "DIN_3") (pintype "passive"))
    )
    (net (code "49") (name "Net-(U46-DOUT)") (class "Default")
      (node (ref "U46") (pin "1") (pinfunction "DOUT_1") (pintype "passive"))
      (node (ref "U47") (pin "3") (pinfunction "DIN_3") (pintype "passive"))
    )
    (net (code "50") (name "Net-(U47-DOUT)") (class "Default")
      (node (ref "U47") (pin "1") (pinfunction "DOUT_1") (pintype "passive"))
      (node (ref "U48") (pin "3") (pinfunction "DIN_3") (pintype "passive"))
    )
    (net (code "51") (name "Net-(U48-DOUT)") (class "Default")
      (node (ref "U48") (pin "1") (pinfunction "DOUT_1") (pintype "passive"))
      (node (ref "U49") (pin "3") (pinfunction "DIN_3") (pintype "passive"))
    )
    (net (code "52") (name "Net-(U49-DOUT)") (class "Default")
      (node (ref "U49") (pin "1") (pinfunction "DOUT_1") (pintype "passive"))
      (node (ref "U50") (pin "3") (pinfunction "DIN_3") (pintype "passive"))
    )
    (net (code "53") (name "Net-(U50-DOUT)") (class "Default")
      (node (ref "U50") (pin "1") (pinfunction "DOUT_1") (pintype "passive"))
      (node (ref "U51") (pin "3") (pinfunction "DIN_3") (pintype "passive"))
    )
    (net (code "54") (name "Net-(U51-DOUT)") (class "Default")
      (node (ref "U51") (pin "1") (pinfunction "DOUT_1") (pintype "passive"))
      (node (ref "U52") (pin "3") (pinfunction "DIN_3") (pintype "passive"))
    )
    (net (code "55") (name "Net-(U52-DOUT)") (class "Default")
      (node (ref "U52") (pin "1") (pinfunction "DOUT_1") (pintype "passive"))
      (node (ref "U53") (pin "3") (pinfunction "DIN_3") (pintype "passive"))
    )
    (net (code "56") (name "Net-(U53-DOUT)") (class "Default")
      (node (ref "U53") (pin "1") (pinfunction "DOUT_1") (pintype "passive"))
      (node (ref "U54") (pin "3") (pinfunction "DIN_3") (pintype "passive"))
    )
    (net (code "57") (name "Net-(U54-DOUT)") (class "Default")
      (node (ref "U54") (pin "1") (pinfunction "DOUT_1") (pintype "passive"))
      (node (ref "U55") (pin "3") (pinfunction "DIN_3") (pintype "passive"))
    )
    (net (code "58") (name "Net-(U55-DOUT)") (class "Default")
      (node (ref "U55") (pin "1") (pinfunction "DOUT_1") (pintype "passive"))
      (node (ref "U56") (pin "3") (pinfunction "DIN_3") (pintype "passive"))
    )
    (net (code "59") (name "Net-(U56-DOUT)") (class "Default")
      (node (ref "U56") (pin "1") (pinfunction "DOUT_1") (pintype "passive"))
      (node (ref "U57") (pin "3") (pinfunction "DIN_3") (pintype "passive"))
    )
    (net (code "60") (name "Net-(U57-DOUT)") (class "Default")
      (node (ref "U57") (pin "1") (pinfunction "DOUT_1") (pintype "passive"))
      (node (ref "U58") (pin "3") (pinfunction "DIN_3") (pintype "passive"))
    )
    (net (code "61") (name "Net-(U58-DOUT)") (class "Default")
      (node (ref "U58") (pin "1") (pinfunction "DOUT_1") (pintype "passive"))
      (node (ref "U59") (pin "3") (pinfunction "DIN_3") (pintype "passive"))
    )
    (net (code "62") (name "Net-(U59-DOUT)") (class "Default")
      (node (ref "U59") (pin "1") (pinfunction "DOUT_1") (pintype "passive"))
      (node (ref "U60") (pin "3") (pinfunction "DIN_3") (pintype "passive"))
    )
    (net (code "63") (name "Net-(U60-DOUT)") (class "Default")
      (node (ref "U60") (pin "1") (pinfunction "DOUT_1") (pintype "passive"))
      (node (ref "U61") (pin "3") (pinfunction "DIN_3") (pintype "passive"))
    )
    (net (code "64") (name "Net-(U61-DOUT)") (class "Default")
      (node (ref "U61") (pin "1") (pinfunction "DOUT_1") (pintype "passive"))
      (node (ref "U62") (pin "3") (pinfunction "DIN_3") (pintype "passive"))
    )
    (net (code "65") (name "Net-(U62-DOUT)") (class "Default")
      (node (ref "U62") (pin "1") (pinfunction "DOUT_1") (pintype "passive"))
      (node (ref "U63") (pin "3") (pinfunction "DIN_3") (pintype "passive"))
    )
    (net (code "66") (name "Net-(U63-DOUT)") (class "Default")
      (node (ref "U63") (pin "1") (pinfunction "DOUT_1") (pintype "passive"))
      (node (ref "U64") (pin "3") (pinfunction "DIN_3") (pintype "passive"))
    )
    (net (code "67") (name "Net-(U64-DOUT)") (class "Default")
      (node (ref "U64") (pin "1") (pinfunction "DOUT_1") (pintype "passive"))
      (node (ref "U65") (pin "3") (pinfunction "DIN_3") (pintype "passive"))
    )
    (net (code "68") (name "Net-(U65-DOUT)") (class "Default")
      (node (ref "U65") (pin "1") (pinfunction "DOUT_1") (pintype "passive"))
      (node (ref "U66") (pin "3") (pinfunction "DIN_3") (pintype "passive"))
    )
    (net (code "69") (name "Net-(U66-DOUT)") (class "Default")
      (node (ref "U66") (pin "1") (pinfunction "DOUT_1") (pintype "passive"))
      (node (ref "U67") (pin "3") (pinfunction "DIN_3") (pintype "passive"))
    )
    (net (code "70") (name "Net-(U67-DOUT)") (class "Default")
      (node (ref "U67") (pin "1") (pinfunction "DOUT_1") (pintype "passive"))
      (node (ref "U68") (pin "3") (pinfunction "DIN_3") (pintype "passive"))
    )
    (net (code "71") (name "Net-(U68-DOUT)") (class "Default")
      (node (ref "U68") (pin "1") (pinfunction "DOUT_1") (pintype "passive"))
      (node (ref "U69") (pin "3") (pinfunction "DIN_3") (pintype "passive"))
    )
    (net (code "72") (name "Net-(U69-DOUT)") (class "Default")
      (node (ref "U69") (pin "1") (pinfunction "DOUT_1") (pintype "passive"))
      (node (ref "U70") (pin "3") (pinfunction "DIN_3") (pintype "passive"))
    )
    (net (code "73") (name "Net-(U70-DOUT)") (class "Default")
      (node (ref "U70") (pin "1") (pinfunction "DOUT_1") (pintype "passive"))
      (node (ref "U71") (pin "3") (pinfunction "DIN_3") (pintype "passive"))
    )
    (net (code "74") (name "Net-(U71-DOUT)") (class "Default")
      (node (ref "U71") (pin "1") (pinfunction "DOUT_1") (pintype "passive"))
      (node (ref "U72") (pin "3") (pinfunction "DIN_3") (pintype "passive"))
    )
    (net (code "75") (name "Net-(U72-DOUT)") (class "Default")
      (node (ref "U72") (pin "1") (pinfunction "DOUT_1") (pintype "passive"))
      (node (ref "U73") (pin "3") (pinfunction "DIN_3") (pintype "passive"))
    )
    (net (code "76") (name "Net-(U73-DOUT)") (class "Default")
      (node (ref "U73") (pin "1") (pinfunction "DOUT_1") (pintype "passive"))
      (node (ref "U74") (pin "3") (pinfunction "DIN_3") (pintype "passive"))
    )
    (net (code "77") (name "Net-(U74-DOUT)") (class "Default")
      (node (ref "U74") (pin "1") (pinfunction "DOUT_1") (pintype "passive"))
      (node (ref "U75") (pin "3") (pinfunction "DIN_3") (pintype "passive"))
    )
    (net (code "78") (name "Net-(U75-DOUT)") (class "Default")
      (node (ref "U75") (pin "1") (pinfunction "DOUT_1") (pintype "passive"))
      (node (ref "U76") (pin "3") (pinfunction "DIN_3") (pintype "passive"))
    )
    (net (code "79") (name "Net-(U76-DOUT)") (class "Default")
      (node (ref "U76") (pin "1") (pinfunction "DOUT_1") (pintype "passive"))
      (node (ref "U77") (pin "3") (pinfunction "DIN_3") (pintype "passive"))
    )
    (net (code "80") (name "Net-(U77-DOUT)") (class "Default")
      (node (ref "U77") (pin "1") (pinfunction "DOUT_1") (pintype "passive"))
      (node (ref "U78") (pin "3") (pinfunction "DIN_3") (pintype "passive"))
    )
    (net (code "81") (name "Net-(U78-DOUT)") (class "Default")
      (node (ref "U78") (pin "1") (pinfunction "DOUT_1") (pintype "passive"))
      (node (ref "U79") (pin "3") (pinfunction "DIN_3") (pintype "passive"))
    )
    (net (code "82") (name "Net-(U79-DOUT)") (class "Default")
      (node (ref "U79") (pin "1") (pinfunction "DOUT_1") (pintype "passive"))
      (node (ref "U80") (pin "3") (pinfunction "DIN_3") (pintype "passive"))
    )
    (net (code "83") (name "Net-(U80-DOUT)") (class "Default")
      (node (ref "U80") (pin "1") (pinfunction "DOUT_1") (pintype "passive"))
      (node (ref "U81") (pin "3") (pinfunction "DIN_3") (pintype "passive"))
    )
    (net (code "84") (name "Net-(U81-DOUT)") (class "Default")
      (node (ref "U81") (pin "1") (pinfunction "DOUT_1") (pintype "passive"))
      (node (ref "U82") (pin "3") (pinfunction "DIN_3") (pintype "passive"))
    )
    (net (code "85") (name "Net-(U82-DOUT)") (class "Default")
      (node (ref "U82") (pin "1") (pinfunction "DOUT_1") (pintype "passive"))
      (node (ref "U83") (pin "3") (pinfunction "DIN_3") (pintype "passive"))
    )
    (net (code "86") (name "Net-(U83-DOUT)") (class "Default")
      (node (ref "U83") (pin "1") (pinfunction "DOUT_1") (pintype "passive"))
      (node (ref "U84") (pin "3") (pinfunction "DIN_3") (pintype "passive"))
    )
    (net (code "87") (name "Net-(U84-DOUT)") (class "Default")
      (node (ref "U84") (pin "1") (pinfunction "DOUT_1") (pintype "passive"))
      (node (ref "U85") (pin "3") (pinfunction "DIN_3") (pintype "passive"))
    )
    (net (code "88") (name "Net-(U85-DOUT)") (class "Default")
      (node (ref "U85") (pin "1") (pinfunction "DOUT_1") (pintype "passive"))
      (node (ref "U86") (pin "3") (pinfunction "DIN_3") (pintype "passive"))
    )
    (net (code "89") (name "Net-(U86-DOUT)") (class "Default")
      (node (ref "U86") (pin "1") (pinfunction "DOUT_1") (pintype "passive"))
      (node (ref "U87") (pin "3") (pinfunction "DIN_3") (pintype "passive"))
    )
    (net (code "90") (name "Net-(U87-DOUT)") (class "Default")
      (node (ref "U87") (pin "1") (pinfunction "DOUT_1") (pintype "passive"))
      (node (ref "U88") (pin "3") (pinfunction "DIN_3") (pintype "passive"))
    )
    (net (code "91") (name "Net-(U88-DOUT)") (class "Default")
      (node (ref "U88") (pin "1") (pinfunction "DOUT_1") (pintype "passive"))
      (node (ref "U89") (pin "3") (pinfunction "DIN_3") (pintype "passive"))
    )
    (net (code "92") (name "Net-(U89-DOUT)") (class "Default")
      (node (ref "U89") (pin "1") (pinfunction "DOUT_1") (pintype "passive"))
      (node (ref "U90") (pin "3") (pinfunction "DIN_3") (pintype "passive"))
    )
    (net (code "93") (name "Net-(U90-DOUT)") (class "Default")
      (node (ref "U90") (pin "1") (pinfunction "DOUT_1") (pintype "passive"))
      (node (ref "U91") (pin "3") (pinfunction "DIN_3") (pintype "passive"))
    )
    (net (code "94") (name "Net-(U91-DOUT)") (class "Default")
      (node (ref "U91") (pin "1") (pinfunction "DOUT_1") (pintype "passive"))
      (node (ref "U92") (pin "3") (pinfunction "DIN_3") (pintype "passive"))
    )
    (net (code "95") (name "Net-(U92-DOUT)") (class "Default")
      (node (ref "U92") (pin "1") (pinfunction "DOUT_1") (pintype "passive"))
      (node (ref "U93") (pin "3") (pinfunction "DIN_3") (pintype "passive"))
    )
    (net (code "96") (name "Net-(U93-DOUT)") (class "Default")
      (node (ref "U93") (pin "1") (pinfunction "DOUT_1") (pintype "passive"))
      (node (ref "U94") (pin "3") (pinfunction "DIN_3") (pintype "passive"))
    )
    (net (code "97") (name "Net-(U94-DOUT)") (class "Default")
      (node (ref "U94") (pin "1") (pinfunction "DOUT_1") (pintype "passive"))
      (node (ref "U95") (pin "3") (pinfunction "DIN_3") (pintype "passive"))
    )
    (net (code "98") (name "Net-(U95-DOUT)") (class "Default")
      (node (ref "U95") (pin "1") (pinfunction "DOUT_1") (pintype "passive"))
      (node (ref "U96") (pin "3") (pinfunction "DIN_3") (pintype "passive"))
    )
    (net (code "99") (name "Net-(U96-DOUT)") (class "Default")
      (node (ref "U96") (pin "1") (pinfunction "DOUT_1") (pintype "passive"))
      (node (ref "U97") (pin "3") (pinfunction "DIN_3") (pintype "passive"))
    )
    (net (code "100") (name "Net-(U97-DOUT)") (class "Default")
      (node (ref "U97") (pin "1") (pinfunction "DOUT_1") (pintype "passive"))
      (node (ref "U98") (pin "3") (pinfunction "DIN_3") (pintype "passive"))
    )
    (net (code "101") (name "Net-(U98-DOUT)") (class "Default")
      (node (ref "U98") (pin "1") (pinfunction "DOUT_1") (pintype "passive"))
      (node (ref "U99") (pin "3") (pinfunction "DIN_3") (pintype "passive"))
    )
    (net (code "102") (name "Net-(U100-DIN)") (class "Default")
      (node (ref "U100") (pin "3") (pinfunction "DIN_3") (pintype "passive"))
      (node (ref "U99") (pin "1") (pinfunction "DOUT_1") (pintype "passive"))
    )
    (net (code "103") (name "Net-(U100-DOUT)") (class "Default")
      (node (ref "U100") (pin "1") (pinfunction "DOUT_1") (pintype "passive"))
      (node (ref "U101") (pin "3") (pinfunction "DIN_3") (pintype "passive"))
    )
    (net (code "104") (name "Net-(U101-DOUT)") (class "Default")
      (node (ref "U101") (pin "1") (pinfunction "DOUT_1") (pintype "passive"))
      (node (ref "U102") (pin "3") (pinfunction "DIN_3") (pintype "passive"))
    )
    (net (code "105") (name "Net-(U102-DOUT)") (class "Default")
      (node (ref "U102") (pin "1") (pinfunction "DOUT_1") (pintype "passive"))
      (node (ref "U103") (pin "3") (pinfunction "DIN_3") (pintype "passive"))
    )
    (net (code "106") (name "Net-(U103-DOUT)") (class "Default")
      (node (ref "U103") (pin "1") (pinfunction "DOUT_1") (pintype "passive"))
      (node (ref "U104") (pin "3") (pinfunction "DIN_3") (pintype "passive"))
    )
    (net (code "107") (name "Net-(U104-DOUT)") (class "Default")
      (node (ref "U104") (pin "1") (pinfunction "DOUT_1") (pintype "passive"))
      (node (ref "U105") (pin "3") (pinfunction "DIN_3") (pintype "passive"))
    )
    (net (code "108") (name "Net-(U105-DOUT)") (class "Default")
      (node (ref "U105") (pin "1") (pinfunction "DOUT_1") (pintype "passive"))
      (node (ref "U106") (pin "3") (pinfunction "DIN_3") (pintype "passive"))
    )
    (net (code "109") (name "Net-(U106-DOUT)") (class "Default")
      (node (ref "U106") (pin "1") (pinfunction "DOUT_1") (pintype "passive"))
      (node (ref "U107") (pin "3") (pinfunction "DIN_3") (pintype "passive"))
    )
    (net (code "110") (name "Net-(U107-DOUT)") (class "Default")
      (node (ref "U107") (pin "1") (pinfunction "DOUT_1") (pintype "passive"))
      (node (ref "U108") (pin "3") (pinfunction "DIN_3") (pintype "passive"))
    )
    (net (code "111") (name "Net-(U108-DOUT)") (class "Default")
      (node (ref "U108") (pin "1") (pinfunction "DOUT_1") (pintype "passive"))
      (node (ref "U109") (pin "3") (pinfunction "DIN_3") (pintype "passive"))
    )
    (net (code "112") (name "Net-(U109-DOUT)") (class "Default")
      (node (ref "U109") (pin "1") (pinfunction "DOUT_1") (pintype "passive"))
      (node (ref "U110") (pin "3") (pinfunction "DIN_3") (pintype "passive"))
    )
    (net (code "113") (name "Net-(U110-DOUT)") (class "Default")
      (node (ref "U110") (pin "1") (pinfunction "DOUT_1") (pintype "passive"))
      (node (ref "U111") (pin "3") (pinfunction "DIN_3") (pintype "passive"))
    )
    (net (code "114") (name "Net-(U111-DOUT)") (class "Default")
      (node (ref "U111") (pin "1") (pinfunction "DOUT_1") (pintype "passive"))
      (node (ref "U112") (pin "3") (pinfunction "DIN_3") (pintype "passive"))
    )
    (net (code "115") (name "Net-(U112-DOUT)") (class "Default")
      (node (ref "U112") (pin "1") (pinfunction "DOUT_1") (pintype "passive"))
      (node (ref "U113") (pin "3") (pinfunction "DIN_3") (pintype "passive"))
    )
    (net (code "116") (name "Net-(U113-DOUT)") (class "Default")
      (node (ref "U113") (pin "1") (pinfunction "DOUT_1") (pintype "passive"))
      (node (ref "U114") (pin "3") (pinfunction "DIN_3") (pintype "passive"))
    )
    (net (code "117") (name "Net-(U114-DOUT)") (class "Default")
      (node (ref "U114") (pin "1") (pinfunction "DOUT_1") (pintype "passive"))
      (node (ref "U115") (pin "3") (pinfunction "DIN_3") (pintype "passive"))
    )
    (net (code "118") (name "Net-(U115-DOUT)") (class "Default")
      (node (ref "U115") (pin "1") (pinfunction "DOUT_1") (pintype "passive"))
      (node (ref "U116") (pin "3") (pinfunction "DIN_3") (pintype "passive"))
    )
    (net (code "119") (name "Net-(U116-DOUT)") (class "Default")
      (node (ref "U116") (pin "1") (pinfunction "DOUT_1") (pintype "passive"))
      (node (ref "U117") (pin "3") (pinfunction "DIN_3") (pintype "passive"))
    )
    (net (code "120") (name "Net-(U117-DOUT)") (class "Default")
      (node (ref "U117") (pin "1") (pinfunction "DOUT_1") (pintype "passive"))
      (node (ref "U118") (pin "3") (pinfunction "DIN_3") (pintype "passive"))
    )
    (net (code "121") (name "Net-(U118-DOUT)") (class "Default")
      (node (ref "U118") (pin "1") (pinfunction "DOUT_1") (pintype "passive"))
      (node (ref "U119") (pin "3") (pinfunction "DIN_3") (pintype "passive"))
    )
    (net (code "122") (name "Net-(U119-DOUT)") (class "Default")
      (node (ref "U119") (pin "1") (pinfunction "DOUT_1") (pintype "passive"))
      (node (ref "U120") (pin "3") (pinfunction "DIN_3") (pintype "passive"))
    )
    (net (code "123") (name "Net-(U120-DOUT)") (class "Default")
      (node (ref "U120") (pin "1") (pinfunction "DOUT_1") (pintype "passive"))
      (node (ref "U121") (pin "3") (pinfunction "DIN_3") (pintype "passive"))
    )
    (net (code "124") (name "Net-(U121-DOUT)") (class "Default")
      (node (ref "U121") (pin "1") (pinfunction "DOUT_1") (pintype "passive"))
      (node (ref "U122") (pin "3") (pinfunction "DIN_3") (pintype "passive"))
    )
    (net (code "125") (name "Net-(U122-DOUT)") (class "Default")
      (node (ref "U122") (pin "1") (pinfunction "DOUT_1") (pintype "passive"))
      (node (ref "U123") (pin "3") (pinfunction "DIN_3") (pintype "passive"))
    )
    (net (code "126") (name "Net-(U123-DOUT)") (class "Default")
      (node (ref "U123") (pin "1") (pinfunction "DOUT_1") (pintype "passive"))
      (node (ref "U124") (pin "3") (pinfunction "DIN_3") (pintype "passive"))
    )
    (net (code "127") (name "Net-(U124-DOUT)") (class "Default")
      (node (ref "U124") (pin "1") (pinfunction "DOUT_1") (pintype "passive"))
      (node (ref "U125") (pin "3") (pinfunction "DIN_3") (pintype "passive"))
    )
    (net (code "128") (name "Net-(U125-DOUT)") (class "Default")
      (node (ref "U125") (pin "1") (pinfunction "DOUT_1") (pintype "passive"))
      (node (ref "U126") (pin "3") (pinfunction "DIN_3") (pintype "passive"))
    )
    (net (code "129") (name "Net-(U126-DOUT)") (class "Default")
      (node (ref "U126") (pin "1") (pinfunction "DOUT_1") (pintype "passive"))
      (node (ref "U127") (pin "3") (pinfunction "DIN_3") (pintype "passive"))
    )
    (net (code "130") (name "Net-(U127-DOUT)") (class "Default")
      (node (ref "U127") (pin "1") (pinfunction "DOUT_1") (pintype "passive"))
      (node (ref "U128") (pin "3") (pinfunction "DIN_3") (pintype "passive"))
    )
    (net (code "131") (name "VCC") (class "Default")
      (node (ref "C1") (pin "2") (pintype "passive"))
      (node (ref "C10") (pin "2") (pintype "passive"))
      (node (ref "C11") (pin "2") (pintype "passive"))
      (node (ref "C12") (pin "2") (pintype "passive"))
      (node (ref "C13") (pin "2") (pintype "passive"))
      (node (ref "C14") (pin "2") (pintype "passive"))
      (node (ref "C15") (pin "2") (pintype "passive"))
      (node (ref "C16") (pin "2") (pintype "passive"))
      (node (ref "C2") (pin "2") (pintype "passive"))
      (node (ref "C3") (pin "2") (pintype "passive"))
      (node (ref "C4") (pin "2") (pintype "passive"))
      (node (ref "C5") (pin "2") (pintype "passive"))
      (node (ref "C6") (pin "2") (pintype "passive"))
      (node (ref "C7") (pin "2") (pintype "passive"))
      (node (ref "C8") (pin "2") (pintype "passive"))
      (node (ref "C9") (pin "2") (pintype "passive"))
      (node (ref "P1") (pin "2") (pinfunction "VCC_2") (pintype "passive"))
      (node (ref "P1") (pin "4") (pinfunction "VCC_4") (pintype "passive"))
      (node (ref "P2") (pin "2") (pinfunction "VCC_2") (pintype "passive"))
      (node (ref "P2") (pin "4") (pinfunction "VCC_4") (pintype "passive"))
      (node (ref "U1") (pin "4") (pinfunction "VDD_4") (pintype "passive"))
      (node (ref "U10") (pin "4") (pinfunction "VDD_4") (pintype "passive"))
      (node (ref "U100") (pin "4") (pinfunction "VDD_4") (pintype "passive"))
      (node (ref "U101") (pin "4") (pinfunction "VDD_4") (pintype "passive"))
      (node (ref "U102") (pin "4") (pinfunction "VDD_4") (pintype "passive"))
      (node (ref "U103") (pin "4") (pinfunction "VDD_4") (pintype "passive"))
      (node (ref "U104") (pin "4") (pinfunction "VDD_4") (pintype "passive"))
      (node (ref "U105") (pin "4") (pinfunction "VDD_4") (pintype "passive"))
      (node (ref "U106") (pin "4") (pinfunction "VDD_4") (pintype "passive"))
      (node (ref "U107") (pin "4") (pinfunction "VDD_4") (pintype "passive"))
      (node (ref "U108") (pin "4") (pinfunction "VDD_4") (pintype "passive"))
      (node (ref "U109") (pin "4") (pinfunction "VDD_4") (pintype "passive"))
      (node (ref "U11") (pin "4") (pinfunction "VDD_4") (pintype "passive"))
      (node (ref "U110") (pin "4") (pinfunction "VDD_4") (pintype "passive"))
      (node (ref "U111") (pin "4") (pinfunction "VDD_4") (pintype "passive"))
      (node (ref "U112") (pin "4") (pinfunction "VDD_4") (pintype "passive"))
      (node (ref "U113") (pin "4") (pinfunction "VDD_4") (pintype "passive"))
      (node (ref "U114") (pin "4") (pinfunction "VDD_4") (pintype "passive"))
      (node (ref "U115") (pin "4") (pinfunction "VDD_4") (pintype "passive"))
      (node (ref "U116") (pin "4") (pinfunction "VDD_4") (pintype "passive"))
      (node (ref "U117") (pin "4") (pinfunction "VDD_4") (pintype "passive"))
      (node (ref "U118") (pin "4") (pinfunction "VDD_4") (pintype "passive"))
      (node (ref "U119") (pin "4") (pinfunction "VDD_4") (pintype "passive"))
      (node (ref "U12") (pin "4") (pinfunction "VDD_4") (pintype "passive"))
      (node (ref "U120") (pin "4") (pinfunction "VDD_4") (pintype "passive"))
      (node (ref "U121") (pin "4") (pinfunction "VDD_4") (pintype "passive"))
      (node (ref "U122") (pin "4") (pinfunction "VDD_4") (pintype "passive"))
      (node (ref "U123") (pin "4") (pinfunction "VDD_4") (pintype "passive"))
      (node (ref "U124") (pin "4") (pinfunction "VDD_4") (pintype "passive"))
      (node (ref "U125") (pin "4") (pinfunction "VDD_4") (pintype "passive"))
      (node (ref "U126") (pin "4") (pinfunction "VDD_4") (pintype "passive"))
      (node (ref "U127") (pin "4") (pinfunction "VDD_4") (pintype "passive"))
      (node (ref "U128") (pin "4") (pinfunction "VDD_4") (pintype "passive"))
      (node (ref "U13") (pin "4") (pinfunction "VDD_4") (pintype "passive"))
      (node (ref "U14") (pin "4") (pinfunction "VDD_4") (pintype "passive"))
      (node (ref "U15") (pin "4") (pinfunction "VDD_4") (pintype "passive"))
      (node (ref "U16") (pin "4") (pinfunction "VDD_4") (pintype "passive"))
      (node (ref "U17") (pin "4") (pinfunction "VDD_4") (pintype "passive"))
      (node (ref "U18") (pin "4") (pinfunction "VDD_4") (pintype "passive"))
      (node (ref "U19") (pin "4") (pinfunction "VDD_4") (pintype "passive"))
      (node (ref "U2") (pin "4") (pinfunction "VDD_4") (pintype "passive"))
      (node (ref "U20") (pin "4") (pinfunction "VDD_4") (pintype "passive"))
      (node (ref "U21") (pin "4") (pinfunction "VDD_4") (pintype "passive"))
      (node (ref "U22") (pin "4") (pinfunction "VDD_4") (pintype "passive"))
      (node (ref "U23") (pin "4") (pinfunction "VDD_4") (pintype "passive"))
      (node (ref "U24") (pin "4") (pinfunction "VDD_4") (pintype "passive"))
      (node (ref "U25") (pin "4") (pinfunction "VDD_4") (pintype "passive"))
      (node (ref "U26") (pin "4") (pinfunction "VDD_4") (pintype "passive"))
      (node (ref "U27") (pin "4") (pinfunction "VDD_4") (pintype "passive"))
      (node (ref "U28") (pin "4") (pinfunction "VDD_4") (pintype "passive"))
      (node (ref "U29") (pin "4") (pinfunction "VDD_4") (pintype "passive"))
      (node (ref "U3") (pin "4") (pinfunction "VDD_4") (pintype "passive"))
      (node (ref "U30") (pin "4") (pinfunction "VDD_4") (pintype "passive"))
      (node (ref "U31") (pin "4") (pinfunction "VDD_4") (pintype "passive"))
      (node (ref "U32") (pin "4") (pinfunction "VDD_4") (pintype "passive"))
      (node (ref "U33") (pin "4") (pinfunction "VDD_4") (pintype "passive"))
      (node (ref "U34") (pin "4") (pinfunction "VDD_4") (pintype "passive"))
      (node (ref "U35") (pin "4") (pinfunction "VDD_4") (pintype "passive"))
      (node (ref "U36") (pin "4") (pinfunction "VDD_4") (pintype "passive"))
      (node (ref "U37") (pin "4") (pinfunction "VDD_4") (pintype "passive"))
      (node (ref "U38") (pin "4") (pinfunction "VDD_4") (pintype "passive"))
      (node (ref "U39") (pin "4") (pinfunction "VDD_4") (pintype "passive"))
      (node (ref "U4") (pin "4") (pinfunction "VDD_4") (pintype "passive"))
      (node (ref "U40") (pin "4") (pinfunction "VDD_4") (pintype "passive"))
      (node (ref "U41") (pin "4") (pinfunction "VDD_4") (pintype "passive"))
      (node (ref "U42") (pin "4") (pinfunction "VDD_4") (pintype "passive"))
      (node (ref "U43") (pin "4") (pinfunction "VDD_4") (pintype "passive"))
      (node (ref "U44") (pin "4") (pinfunction "VDD_4") (pintype "passive"))
      (node (ref "U45") (pin "4") (pinfunction "VDD_4") (pintype "passive"))
      (node (ref "U46") (pin "4") (pinfunction "VDD_4") (pintype "passive"))
      (node (ref "U47") (pin "4") (pinfunction "VDD_4") (pintype "passive"))
      (node (ref "U48") (pin "4") (pinfunction "VDD_4") (pintype "passive"))
      (node (ref "U49") (pin "4") (pinfunction "VDD_4") (pintype "passive"))
      (node (ref "U5") (pin "4") (pinfunction "VDD_4") (pintype "passive"))
      (node (ref "U50") (pin "4") (pinfunction "VDD_4") (pintype "passive"))
      (node (ref "U51") (pin "4") (pinfunction "VDD_4") (pintype "passive"))
      (node (ref "U52") (pin "4") (pinfunction "VDD_4") (pintype "passive"))
      (node (ref "U53") (pin "4") (pinfunction "VDD_4") (pintype "passive"))
      (node (ref "U54") (pin "4") (pinfunction "VDD_4") (pintype "passive"))
      (node (ref "U55") (pin "4") (pinfunction "VDD_4") (pintype "passive"))
      (node (ref "U56") (pin "4") (pinfunction "VDD_4") (pintype "passive"))
      (node (ref "U57") (pin "4") (pinfunction "VDD_4") (pintype "passive"))
      (node (ref "U58") (pin "4") (pinfunction "VDD_4") (pintype "passive"))
      (node (ref "U59") (pin "4") (pinfunction "VDD_4") (pintype "passive"))
      (node (ref "U6") (pin "4") (pinfunction "VDD_4") (pintype "passive"))
      (node (ref "U60") (pin "4") (pinfunction "VDD_4") (pintype "passive"))
      (node (ref "U61") (pin "4") (pinfunction "VDD_4") (pintype "passive"))
      (node (ref "U62") (pin "4") (pinfunction "VDD_4") (pintype "passive"))
      (node (ref "U63") (pin "4") (pinfunction "VDD_4") (pintype "passive"))
      (node (ref "U64") (pin "4") (pinfunction "VDD_4") (pintype "passive"))
      (node (ref "U65") (pin "4") (pinfunction "VDD_4") (pintype "passive"))
      (node (ref "U66") (pin "4") (pinfunction "VDD_4") (pintype "passive"))
      (node (ref "U67") (pin "4") (pinfunction "VDD_4") (pintype "passive"))
      (node (ref "U68") (pin "4") (pinfunction "VDD_4") (pintype "passive"))
      (node (ref "U69") (pin "4") (pinfunction "VDD_4") (pintype "passive"))
      (node (ref "U7") (pin "4") (pinfunction "VDD_4") (pintype "passive"))
      (node (ref "U70") (pin "4") (pinfunction "VDD_4") (pintype "passive"))
      (node (ref "U71") (pin "4") (pinfunction "VDD_4") (pintype "passive"))
      (node (ref "U72") (pin "4") (pinfunction "VDD_4") (pintype "passive"))
      (node (ref "U73") (pin "4") (pinfunction "VDD_4") (pintype "passive"))
      (node (ref "U74") (pin "4") (pinfunction "VDD_4") (pintype "passive"))
      (node (ref "U75") (pin "4") (pinfunction "VDD_4") (pintype "passive"))
      (node (ref "U76") (pin "4") (pinfunction "VDD_4") (pintype "passive"))
      (node (ref "U77") (pin "4") (pinfunction "VDD_4") (pintype "passive"))
      (node (ref "U78") (pin "4") (pinfunction "VDD_4") (pintype "passive"))
      (node (ref "U79") (pin "4") (pinfunction "VDD_4") (pintype "passive"))
      (node (ref "U8") (pin "4") (pinfunction "VDD_4") (pintype "passive"))
      (node (ref "U80") (pin "4") (pinfunction "VDD_4") (pintype "passive"))
      (node (ref "U81") (pin "4") (pinfunction "VDD_4") (pintype "passive"))
      (node (ref "U82") (pin "4") (pinfunction "VDD_4") (pintype "passive"))
      (node (ref "U83") (pin "4") (pinfunction "VDD_4") (pintype "passive"))
      (node (ref "U84") (pin "4") (pinfunction "VDD_4") (pintype "passive"))
      (node (ref "U85") (pin "4") (pinfunction "VDD_4") (pintype "passive"))
      (node (ref "U86") (pin "4") (pinfunction "VDD_4") (pintype "passive"))
      (node (ref "U87") (pin "4") (pinfunction "VDD_4") (pintype "passive"))
      (node (ref "U88") (pin "4") (pinfunction "VDD_4") (pintype "passive"))
      (node (ref "U89") (pin "4") (pinfunction "VDD_4") (pintype "passive"))
      (node (ref "U9") (pin "4") (pinfunction "VDD_4") (pintype "passive"))
      (node (ref "U90") (pin "4") (pinfunction "VDD_4") (pintype "passive"))
      (node (ref "U91") (pin "4") (pinfunction "VDD_4") (pintype "passive"))
      (node (ref "U92") (pin "4") (pinfunction "VDD_4") (pintype "passive"))
      (node (ref "U93") (pin "4") (pinfunction "VDD_4") (pintype "passive"))
      (node (ref "U94") (pin "4") (pinfunction "VDD_4") (pintype "passive"))
      (node (ref "U95") (pin "4") (pinfunction "VDD_4") (pintype "passive"))
      (node (ref "U96") (pin "4") (pinfunction "VDD_4") (pintype "passive"))
      (node (ref "U97") (pin "4") (pinfunction "VDD_4") (pintype "passive"))
      (node (ref "U98") (pin "4") (pinfunction "VDD_4") (pintype "passive"))
      (node (ref "U99") (pin "4") (pinfunction "VDD_4") (pintype "passive"))
    )
  )
)
